# esp8266-board.net
KiCad netlist of a schematic drawn in EAGLE
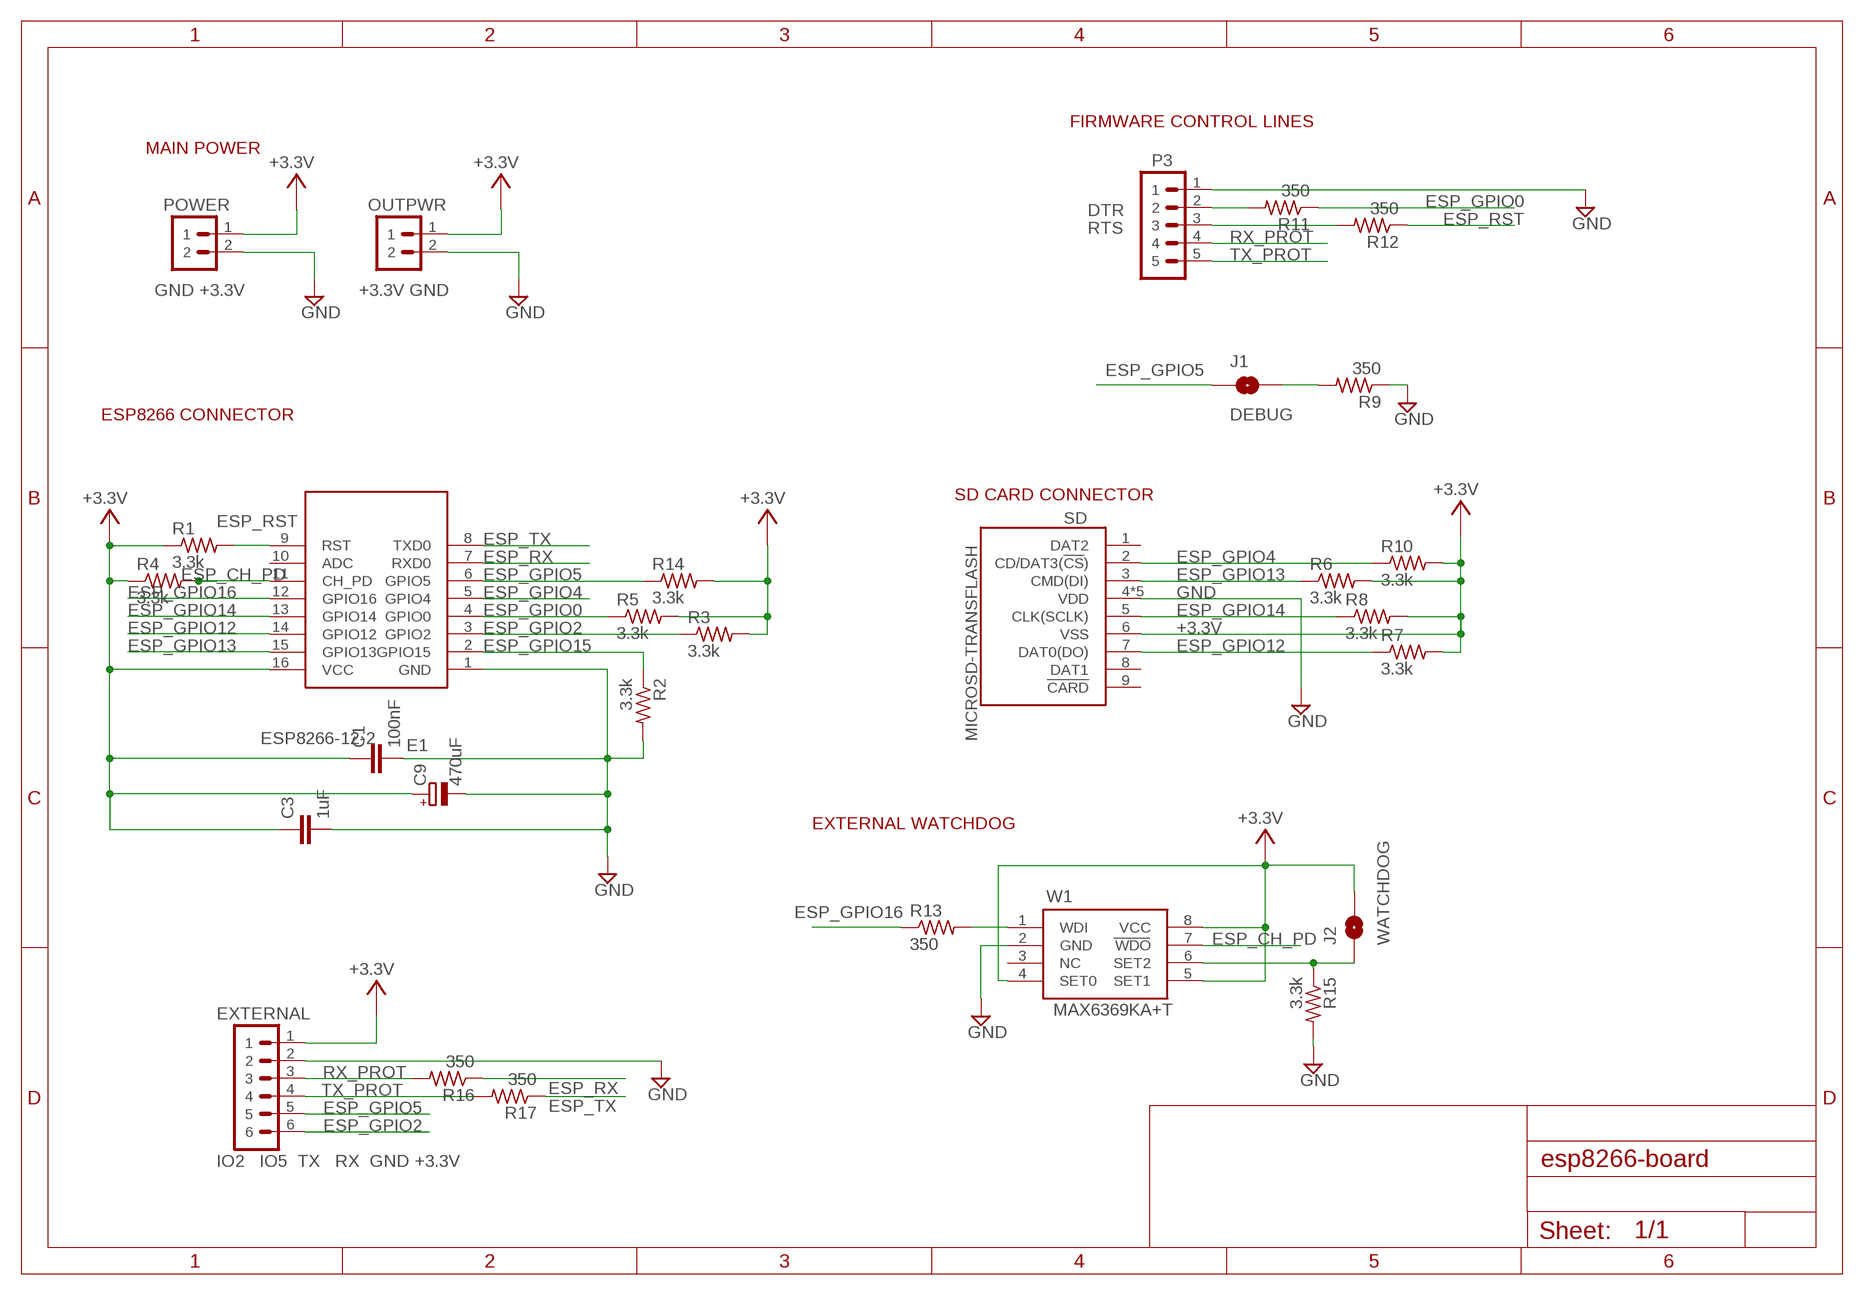
[diagram p0: schematic, sheet 1]

(export (version "E")
  (design (tool "Eeschema 10.0.6"))
  (components
    (comp (ref "C1")
      (value "100nF")
      (footprint "eagle-import:SMD0805")
      (libsource (lib "eagle-import") (part "CAPACITOR0805"))
    )
    (comp (ref "C3")
      (value "1uF")
      (footprint "eagle-import:SMD0805")
      (libsource (lib "eagle-import") (part "CAPACITOR0805"))
    )
    (comp (ref "C9")
      (value "470uF")
      (footprint "eagle-import:E2,5-6")
      (libsource (lib "eagle-import") (part "CPOL-EUE2.5-6"))
    )
    (comp (ref "E1")
      (value "ESP8266-12-2")
      (footprint "eagle-import:ESP8266-12-2")
      (libsource (lib "eagle-import") (part "ESP8266-12-2"))
    )
    (comp (ref "EXTERNAL")
      (value "IO2 IO5 TX RX GND +3.3V")
      (footprint "eagle-import:PIN-HEADER-6PIN")
      (libsource (lib "eagle-import") (part "PIN-HEADER-6PIN"))
    )
    (comp (ref "J1")
      (value "DEBUG")
      (footprint "eagle-import:JUMPER-PAD-2-ROUND")
      (libsource (lib "eagle-import") (part "JUMPER-PAD-2ROUND"))
    )
    (comp (ref "J2")
      (value "WATCHDOG")
      (footprint "eagle-import:JUMPER-PAD-2-ROUND")
      (libsource (lib "eagle-import") (part "JUMPER-PAD-2ROUND"))
    )
    (comp (ref "OUTPWR")
      (value "+3.3V GND")
      (footprint "eagle-import:PIN-HEADER-2PIN")
      (libsource (lib "eagle-import") (part "PIN-HEADER-2PIN"))
    )
    (comp (ref "P3")
      (value "GND DTR RTS RX TX")
      (footprint "eagle-import:PIN-HEADER-5PIN")
      (libsource (lib "eagle-import") (part "PIN-HEADER-5PIN"))
    )
    (comp (ref "POWER")
      (value "GND +3.3V")
      (footprint "eagle-import:PIN-HEADER-2PIN")
      (libsource (lib "eagle-import") (part "PIN-HEADER-2PIN"))
    )
    (comp (ref "R1")
      (value "3.3k")
      (footprint "eagle-import:SMD0805")
      (libsource (lib "eagle-import") (part "RESISTOR0805"))
    )
    (comp (ref "R2")
      (value "3.3k")
      (footprint "eagle-import:SMD0805")
      (libsource (lib "eagle-import") (part "RESISTOR0805"))
    )
    (comp (ref "R3")
      (value "3.3k")
      (footprint "eagle-import:SMD0805")
      (libsource (lib "eagle-import") (part "RESISTOR0805"))
    )
    (comp (ref "R4")
      (value "3.3k")
      (footprint "eagle-import:SMD0805")
      (libsource (lib "eagle-import") (part "RESISTOR0805"))
    )
    (comp (ref "R5")
      (value "3.3k")
      (footprint "eagle-import:SMD0805")
      (libsource (lib "eagle-import") (part "RESISTOR0805"))
    )
    (comp (ref "R6")
      (value "3.3k")
      (footprint "eagle-import:SMD0805")
      (libsource (lib "eagle-import") (part "RESISTOR0805"))
    )
    (comp (ref "R7")
      (value "3.3k")
      (footprint "eagle-import:SMD0805")
      (libsource (lib "eagle-import") (part "RESISTOR0805"))
    )
    (comp (ref "R8")
      (value "3.3k")
      (footprint "eagle-import:SMD0805")
      (libsource (lib "eagle-import") (part "RESISTOR0805"))
    )
    (comp (ref "R9")
      (value "350")
      (footprint "eagle-import:SMD0805")
      (libsource (lib "eagle-import") (part "RESISTOR0805"))
    )
    (comp (ref "R10")
      (value "3.3k")
      (footprint "eagle-import:SMD0805")
      (libsource (lib "eagle-import") (part "RESISTOR0805"))
    )
    (comp (ref "R11")
      (value "350")
      (footprint "eagle-import:SMD0805")
      (libsource (lib "eagle-import") (part "RESISTOR0805"))
    )
    (comp (ref "R12")
      (value "350")
      (footprint "eagle-import:SMD0805")
      (libsource (lib "eagle-import") (part "RESISTOR0805"))
    )
    (comp (ref "R13")
      (value "350")
      (footprint "eagle-import:SMD0805")
      (libsource (lib "eagle-import") (part "RESISTOR0805"))
    )
    (comp (ref "R14")
      (value "3.3k")
      (footprint "eagle-import:SMD0805")
      (libsource (lib "eagle-import") (part "RESISTOR0805"))
    )
    (comp (ref "R15")
      (value "3.3k")
      (footprint "eagle-import:SMD0805")
      (libsource (lib "eagle-import") (part "RESISTOR0805"))
    )
    (comp (ref "R16")
      (value "350")
      (footprint "eagle-import:SMD0805")
      (libsource (lib "eagle-import") (part "RESISTOR0805"))
    )
    (comp (ref "R17")
      (value "350")
      (footprint "eagle-import:SMD0805")
      (libsource (lib "eagle-import") (part "RESISTOR0805"))
    )
    (comp (ref "SD")
      (value "MICROSD-TRANSFLASH")
      (footprint "eagle-import:MICROSD-TRANSFLASH")
      (libsource (lib "eagle-import") (part "MICROSD-TRANSFLASH"))
    )
    (comp (ref "W1")
      (value "MAX6369KA+T")
      (footprint "eagle-import:SOT23-8")
      (libsource (lib "eagle-import") (part "MAX6369-74"))
    )
  )
  (nets
    (net (code "1") (name "+3.3V") (class "Default")
      (node (ref "C1") (pin "1") (pinfunction "1_1") (pintype "passive"))
      (node (ref "C3") (pin "1") (pinfunction "1_1") (pintype "passive"))
      (node (ref "C9") (pin "+") (pinfunction "+_+") (pintype "passive"))
      (node (ref "E1") (pin "16") (pinfunction "VCC_16") (pintype "power_in"))
      (node (ref "EXTERNAL") (pin "1") (pinfunction "1_1") (pintype "passive"))
      (node (ref "J2") (pin "2") (pinfunction "2_2") (pintype "passive"))
      (node (ref "OUTPWR") (pin "1") (pinfunction "1_1") (pintype "passive"))
      (node (ref "POWER") (pin "1") (pinfunction "1_1") (pintype "passive"))
      (node (ref "R1") (pin "1") (pinfunction "1_1") (pintype "passive"))
      (node (ref "R10") (pin "2") (pinfunction "2_2") (pintype "passive"))
      (node (ref "R14") (pin "2") (pinfunction "2_2") (pintype "passive"))
      (node (ref "R3") (pin "2") (pinfunction "2_2") (pintype "passive"))
      (node (ref "R4") (pin "1") (pinfunction "1_1") (pintype "passive"))
      (node (ref "R5") (pin "2") (pinfunction "2_2") (pintype "passive"))
      (node (ref "R6") (pin "2") (pinfunction "2_2") (pintype "passive"))
      (node (ref "R7") (pin "2") (pinfunction "2_2") (pintype "passive"))
      (node (ref "R8") (pin "2") (pinfunction "2_2") (pintype "passive"))
      (node (ref "SD") (pin "6") (pinfunction "VSS_6") (pintype "power_in"))
      (node (ref "W1") (pin "4") (pinfunction "SET0_4") (pintype "input"))
      (node (ref "W1") (pin "5") (pinfunction "SET1_5") (pintype "input"))
      (node (ref "W1") (pin "8") (pinfunction "VCC_8") (pintype "power_in"))
    )
    (net (code "2") (name "/ESP_CH_PD") (class "Default")
      (node (ref "E1") (pin "11") (pinfunction "CH_PD_11") (pintype "input"))
      (node (ref "R4") (pin "2") (pinfunction "2_2") (pintype "passive"))
      (node (ref "W1") (pin "7") (pinfunction "WDO_7") (pintype "output"))
    )
    (net (code "3") (name "/ESP_GPIO0") (class "Default")
      (node (ref "E1") (pin "4") (pinfunction "GPIO0_4") (pintype "bidirectional"))
      (node (ref "R11") (pin "1") (pinfunction "1_1") (pintype "passive"))
      (node (ref "R5") (pin "1") (pinfunction "1_1") (pintype "passive"))
    )
    (net (code "4") (name "/ESP_GPIO2") (class "Default")
      (node (ref "E1") (pin "3") (pinfunction "GPIO2_3") (pintype "bidirectional"))
      (node (ref "EXTERNAL") (pin "6") (pinfunction "6_6") (pintype "passive"))
      (node (ref "R3") (pin "1") (pinfunction "1_1") (pintype "passive"))
    )
    (net (code "5") (name "/ESP_GPIO4") (class "Default")
      (node (ref "E1") (pin "5") (pinfunction "GPIO4_5") (pintype "bidirectional"))
      (node (ref "R10") (pin "1") (pinfunction "1_1") (pintype "passive"))
      (node (ref "SD") (pin "2") (pinfunction "CD/DAT3(~{CS})_2") (pintype "bidirectional"))
    )
    (net (code "6") (name "/ESP_GPIO5") (class "Default")
      (node (ref "E1") (pin "6") (pinfunction "GPIO5_6") (pintype "bidirectional"))
      (node (ref "EXTERNAL") (pin "5") (pinfunction "5_5") (pintype "passive"))
      (node (ref "J1") (pin "1") (pinfunction "1_1") (pintype "passive"))
      (node (ref "R14") (pin "1") (pinfunction "1_1") (pintype "passive"))
    )
    (net (code "7") (name "/ESP_GPIO12") (class "Default")
      (node (ref "E1") (pin "14") (pinfunction "GPIO12_14") (pintype "bidirectional"))
      (node (ref "R7") (pin "1") (pinfunction "1_1") (pintype "passive"))
      (node (ref "SD") (pin "7") (pinfunction "DAT0(DO)_7") (pintype "bidirectional"))
    )
    (net (code "8") (name "/ESP_GPIO13") (class "Default")
      (node (ref "E1") (pin "15") (pinfunction "GPIO13_15") (pintype "bidirectional"))
      (node (ref "R6") (pin "1") (pinfunction "1_1") (pintype "passive"))
      (node (ref "SD") (pin "3") (pinfunction "CMD(DI)_3") (pintype "bidirectional"))
    )
    (net (code "9") (name "/ESP_GPIO14") (class "Default")
      (node (ref "E1") (pin "13") (pinfunction "GPIO14_13") (pintype "bidirectional"))
      (node (ref "R8") (pin "1") (pinfunction "1_1") (pintype "passive"))
      (node (ref "SD") (pin "5") (pinfunction "CLK(SCLK)_5") (pintype "input"))
    )
    (net (code "10") (name "/ESP_GPIO15") (class "Default")
      (node (ref "E1") (pin "2") (pinfunction "GPIO15_2") (pintype "bidirectional"))
      (node (ref "R2") (pin "1") (pinfunction "1_1") (pintype "passive"))
    )
    (net (code "11") (name "/ESP_GPIO16") (class "Default")
      (node (ref "E1") (pin "12") (pinfunction "GPIO16_12") (pintype "bidirectional"))
      (node (ref "R13") (pin "1") (pinfunction "1_1") (pintype "passive"))
    )
    (net (code "12") (name "/ESP_RST") (class "Default")
      (node (ref "E1") (pin "9") (pinfunction "RST_9") (pintype "input"))
      (node (ref "R1") (pin "2") (pinfunction "2_2") (pintype "passive"))
      (node (ref "R12") (pin "1") (pinfunction "1_1") (pintype "passive"))
    )
    (net (code "13") (name "/ESP_RX") (class "Default")
      (node (ref "E1") (pin "7") (pinfunction "RXD0_7") (pintype "input"))
      (node (ref "R16") (pin "1") (pinfunction "1_1") (pintype "passive"))
    )
    (net (code "14") (name "/ESP_TX") (class "Default")
      (node (ref "E1") (pin "8") (pinfunction "TXD0_8") (pintype "output"))
      (node (ref "R17") (pin "1") (pinfunction "1_1") (pintype "passive"))
    )
    (net (code "15") (name "/RX_PROT") (class "Default")
      (node (ref "EXTERNAL") (pin "3") (pinfunction "3_3") (pintype "passive"))
      (node (ref "P3") (pin "4") (pinfunction "4_4") (pintype "passive"))
      (node (ref "R16") (pin "2") (pinfunction "2_2") (pintype "passive"))
    )
    (net (code "16") (name "/TX_PROT") (class "Default")
      (node (ref "EXTERNAL") (pin "4") (pinfunction "4_4") (pintype "passive"))
      (node (ref "P3") (pin "5") (pinfunction "5_5") (pintype "passive"))
      (node (ref "R17") (pin "2") (pinfunction "2_2") (pintype "passive"))
    )
    (net (code "17") (name "GND") (class "Default")
      (node (ref "C1") (pin "2") (pinfunction "2_2") (pintype "passive"))
      (node (ref "C3") (pin "2") (pinfunction "2_2") (pintype "passive"))
      (node (ref "C9") (pin "-") (pinfunction "-_-") (pintype "passive"))
      (node (ref "E1") (pin "1") (pinfunction "GND_1") (pintype "power_in"))
      (node (ref "EXTERNAL") (pin "2") (pinfunction "2_2") (pintype "passive"))
      (node (ref "OUTPWR") (pin "2") (pinfunction "2_2") (pintype "passive"))
      (node (ref "P3") (pin "1") (pinfunction "1_1") (pintype "passive"))
      (node (ref "POWER") (pin "2") (pinfunction "2_2") (pintype "passive"))
      (node (ref "R15") (pin "2") (pinfunction "2_2") (pintype "passive"))
      (node (ref "R2") (pin "2") (pinfunction "2_2") (pintype "passive"))
      (node (ref "R9") (pin "1") (pinfunction "1_1") (pintype "passive"))
      (node (ref "SD") (pin "4") (pinfunction "VDD_4") (pintype "power_in"))
      (node (ref "SD") (pin "S1") (pinfunction "VDD_S1") (pintype "power_in"))
      (node (ref "SD") (pin "S2") (pinfunction "VDD_S2") (pintype "power_in"))
      (node (ref "SD") (pin "S3") (pinfunction "VDD_S3") (pintype "power_in"))
      (node (ref "SD") (pin "S4") (pinfunction "VDD_S4") (pintype "power_in"))
      (node (ref "W1") (pin "2") (pinfunction "GND_2") (pintype "power_in"))
    )
    (net (code "18") (name "Net-(J1-Pad2)") (class "Default")
      (node (ref "J1") (pin "2") (pinfunction "2_2") (pintype "passive"))
      (node (ref "R9") (pin "2") (pinfunction "2_2") (pintype "passive"))
    )
    (net (code "19") (name "Net-(P3-Pad2)") (class "Default")
      (node (ref "P3") (pin "2") (pinfunction "2_2") (pintype "passive"))
      (node (ref "R11") (pin "2") (pinfunction "2_2") (pintype "passive"))
    )
    (net (code "20") (name "Net-(P3-Pad3)") (class "Default")
      (node (ref "P3") (pin "3") (pinfunction "3_3") (pintype "passive"))
      (node (ref "R12") (pin "2") (pinfunction "2_2") (pintype "passive"))
    )
    (net (code "21") (name "Net-(W1-SET2)") (class "Default")
      (node (ref "J2") (pin "1") (pinfunction "1_1") (pintype "passive"))
      (node (ref "R15") (pin "1") (pinfunction "1_1") (pintype "passive"))
      (node (ref "W1") (pin "6") (pinfunction "SET2_6") (pintype "input"))
    )
    (net (code "22") (name "Net-(W1-WDI)") (class "Default")
      (node (ref "R13") (pin "2") (pinfunction "2_2") (pintype "passive"))
      (node (ref "W1") (pin "1") (pinfunction "WDI_1") (pintype "input"))
    )
    (net (code "23") (name "unconnected-(E1-ADC-Pad10)") (class "Default")
      (node (ref "E1") (pin "10") (pinfunction "ADC_10") (pintype "input"))
    )
    (net (code "24") (name "unconnected-(SD-DAT1-Pad8)") (class "Default")
      (node (ref "SD") (pin "8") (pinfunction "DAT1_8") (pintype "bidirectional"))
    )
    (net (code "25") (name "unconnected-(SD-DAT2-Pad1)") (class "Default")
      (node (ref "SD") (pin "1") (pinfunction "DAT2_1") (pintype "bidirectional"))
    )
    (net (code "26") (name "unconnected-(SD-~{CARD}-Pad9)") (class "Default")
      (node (ref "SD") (pin "9") (pinfunction "~{CARD}_9") (pintype "passive"))
    )
    (net (code "27") (name "unconnected-(W1-NC-Pad3)") (class "Default")
      (node (ref "W1") (pin "3") (pinfunction "NC_3") (pintype "no_connect"))
    )
  )
)
